# F1C100S.net
KiCad netlist of a schematic drawn in Altium Designer
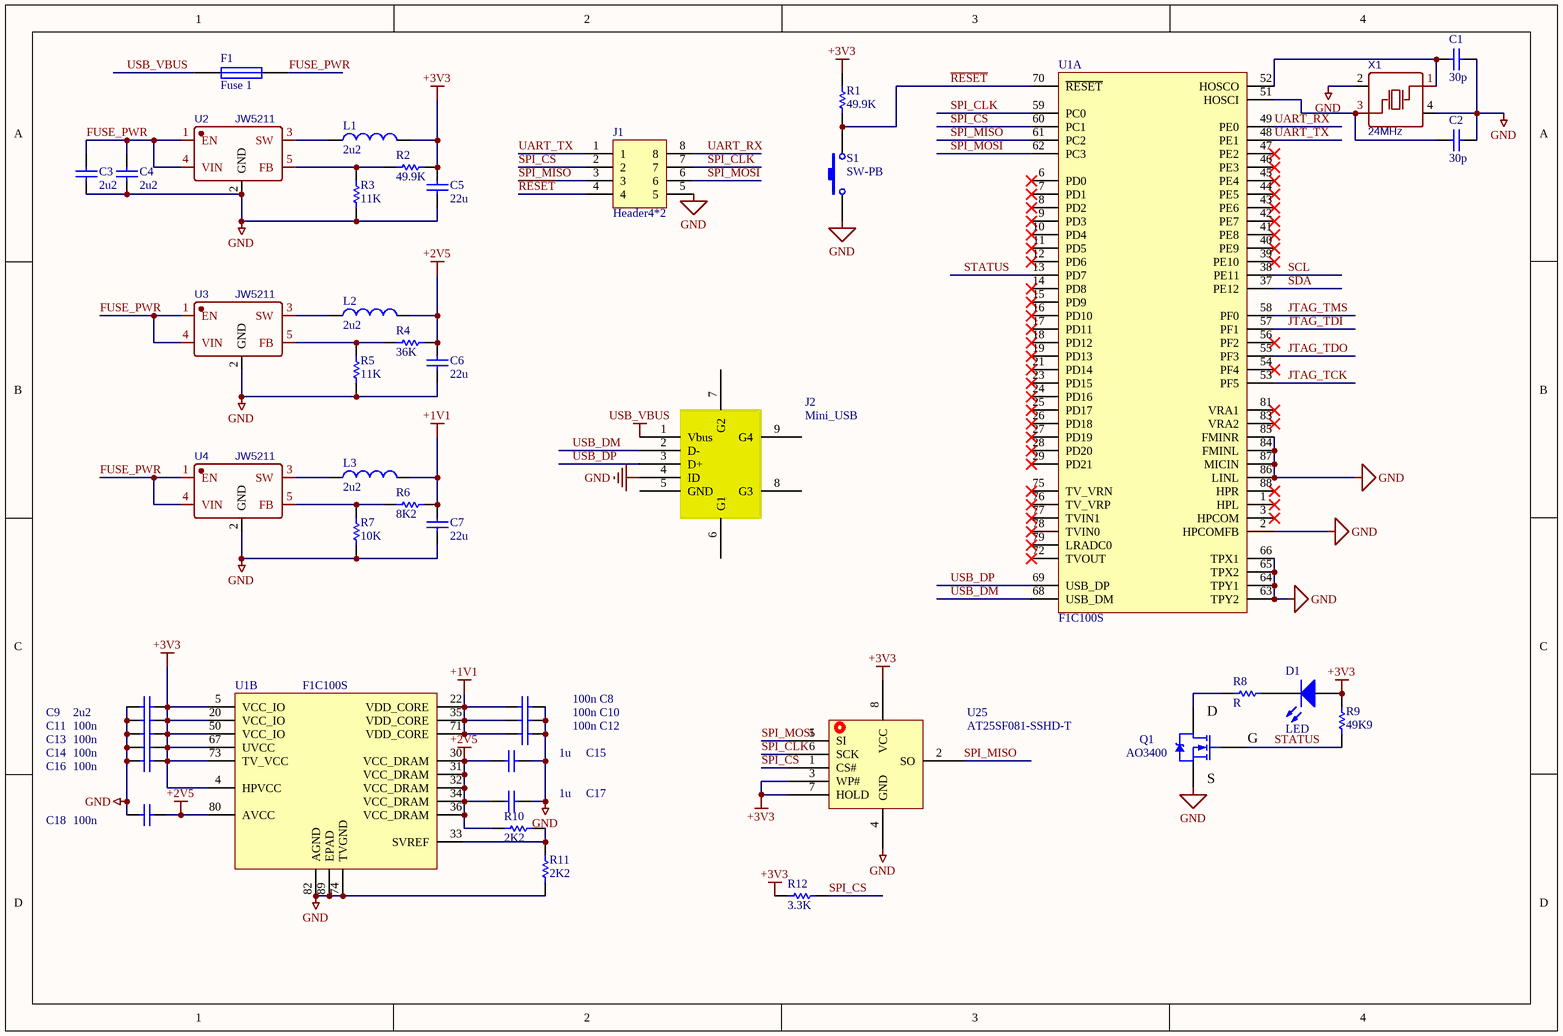
[diagram p0: 树莓派F1C100S.SchDoc]

(export (version "E")
  (design (tool "Eeschema 10.0.6"))
  (components
    (comp (ref "C1")
      (value "30p")
      (footprint "C0805")
      (description "Capacitor")
      (fields (field (name "PUBLISHER") "Altium Limited"))
      (libsource (lib "Miscellaneous Devices") (part "Cap"))
    )
    (comp (ref "C2")
      (value "30p")
      (footprint "C0805")
      (description "Capacitor")
      (fields (field (name "PUBLISHER") "Altium Limited"))
      (libsource (lib "Miscellaneous Devices") (part "Cap"))
    )
    (comp (ref "C3")
      (value "2u2")
      (footprint "C0805")
      (description "Capacitor")
      (fields (field (name "PUBLISHER") "Altium Limited"))
      (libsource (lib "Miscellaneous Devices") (part "Cap"))
    )
    (comp (ref "C4")
      (value "2u2")
      (footprint "C0805")
      (description "Capacitor")
      (fields (field (name "PUBLISHER") "Altium Limited"))
      (libsource (lib "Miscellaneous Devices") (part "Cap"))
    )
    (comp (ref "C5")
      (value "22u")
      (footprint "C0805")
      (description "Capacitor")
      (fields (field (name "PUBLISHER") "Altium Limited"))
      (libsource (lib "Miscellaneous Devices") (part "Cap"))
    )
    (comp (ref "C6")
      (value "22u")
      (footprint "C0805")
      (description "Capacitor")
      (fields (field (name "PUBLISHER") "Altium Limited"))
      (libsource (lib "Miscellaneous Devices") (part "Cap"))
    )
    (comp (ref "C7")
      (value "22u")
      (footprint "C0805")
      (description "Capacitor")
      (fields (field (name "PUBLISHER") "Altium Limited"))
      (libsource (lib "Miscellaneous Devices") (part "Cap"))
    )
    (comp (ref "C8")
      (value "100n")
      (footprint "C0805")
      (description "Capacitor")
      (fields (field (name "PUBLISHER") "Altium Limited"))
      (libsource (lib "Miscellaneous Devices") (part "Cap"))
    )
    (comp (ref "C9")
      (value "2u2")
      (footprint "C0805")
      (description "Capacitor")
      (fields (field (name "PUBLISHER") "Altium Limited"))
      (libsource (lib "Miscellaneous Devices") (part "Cap"))
    )
    (comp (ref "C10")
      (value "100n")
      (footprint "C0805")
      (description "Capacitor")
      (fields (field (name "PUBLISHER") "Altium Limited"))
      (libsource (lib "Miscellaneous Devices") (part "Cap"))
    )
    (comp (ref "C11")
      (value "100n")
      (footprint "C0805")
      (description "Capacitor")
      (fields (field (name "PUBLISHER") "Altium Limited"))
      (libsource (lib "Miscellaneous Devices") (part "Cap"))
    )
    (comp (ref "C12")
      (value "100n")
      (footprint "C0805")
      (description "Capacitor")
      (fields (field (name "PUBLISHER") "Altium Limited"))
      (libsource (lib "Miscellaneous Devices") (part "Cap"))
    )
    (comp (ref "C13")
      (value "100n")
      (footprint "C0805")
      (description "Capacitor")
      (fields (field (name "PUBLISHER") "Altium Limited"))
      (libsource (lib "Miscellaneous Devices") (part "Cap"))
    )
    (comp (ref "C14")
      (value "100n")
      (footprint "C0805")
      (description "Capacitor")
      (fields (field (name "PUBLISHER") "Altium Limited"))
      (libsource (lib "Miscellaneous Devices") (part "Cap"))
    )
    (comp (ref "C15")
      (value "1u")
      (footprint "C0805")
      (description "Capacitor")
      (fields (field (name "PUBLISHER") "Altium Limited"))
      (libsource (lib "Miscellaneous Devices") (part "Cap"))
    )
    (comp (ref "C16")
      (value "100n")
      (footprint "C0805")
      (description "Capacitor")
      (fields (field (name "PUBLISHER") "Altium Limited"))
      (libsource (lib "Miscellaneous Devices") (part "Cap"))
    )
    (comp (ref "C17")
      (value "1u")
      (footprint "C0805")
      (description "Capacitor")
      (fields (field (name "PUBLISHER") "Altium Limited"))
      (libsource (lib "Miscellaneous Devices") (part "Cap"))
    )
    (comp (ref "C18")
      (value "100n")
      (footprint "C0805")
      (description "Capacitor")
      (fields (field (name "PUBLISHER") "Altium Limited"))
      (libsource (lib "Miscellaneous Devices") (part "Cap"))
    )
    (comp (ref "D1")
      (value "LED")
      (footprint "LED-0805")
      (description "Typical INFRARED GaAs LED")
      (fields (field (name "PUBLISHER") "Altium Limited"))
      (libsource (lib "SZ") (part "LED0"))
    )
    (comp (ref "F1")
      (value "Fuse 1")
      (footprint "polyfuse")
      (description "Fuse")
      (fields (field (name "PUBLISHER") "Altium Limited"))
      (libsource (lib "Miscellaneous Devices") (part "Fuse 1"))
    )
    (comp (ref "J1") (value "Header4*2") (footprint "HDR2X4") (libsource (lib "SZ") (part "Header4*2")))
    (comp (ref "J2") (value "Mini_USB") (footprint "MINi_USB_2") (libsource (lib "*") (part "Mini_USB")))
    (comp (ref "L1")
      (value "2u2")
      (footprint "R0805")
      (description "Inductor")
      (fields (field (name "PUBLISHER") "Altium Limited"))
      (libsource (lib "Miscellaneous Devices") (part "Inductor"))
    )
    (comp (ref "L2")
      (value "2u2")
      (footprint "R0805")
      (description "Inductor")
      (fields (field (name "PUBLISHER") "Altium Limited"))
      (libsource (lib "Miscellaneous Devices") (part "Inductor"))
    )
    (comp (ref "L3")
      (value "2u2")
      (footprint "R0805")
      (description "Inductor")
      (fields (field (name "PUBLISHER") "Altium Limited"))
      (libsource (lib "Miscellaneous Devices") (part "Inductor"))
    )
    (comp (ref "Q1")
      (value "AO3400")
      (footprint "SOT-23")
      (description "N-Channel Power MOSFET")
      (fields (field (name "PUBLISHER") "Altium Limited"))
      (libsource (lib "SZ") (part "AO3400"))
    )
    (comp (ref "R1")
      (value "49.9K")
      (footprint "R0805")
      (description "Resistor")
      (fields (field (name "PUBLISHER") "Altium Limited"))
      (libsource (lib "Miscellaneous Devices") (part "Res1"))
    )
    (comp (ref "R2")
      (value "49.9K")
      (footprint "R0805")
      (description "Resistor")
      (fields (field (name "PUBLISHER") "Altium Limited"))
      (libsource (lib "Miscellaneous Devices") (part "Res1"))
    )
    (comp (ref "R3")
      (value "11K")
      (footprint "R0805")
      (description "Resistor")
      (fields (field (name "PUBLISHER") "Altium Limited"))
      (libsource (lib "Miscellaneous Devices") (part "Res1"))
    )
    (comp (ref "R4")
      (value "36K")
      (footprint "R0805")
      (description "Resistor")
      (fields (field (name "PUBLISHER") "Altium Limited"))
      (libsource (lib "Miscellaneous Devices") (part "Res1"))
    )
    (comp (ref "R5")
      (value "11K")
      (footprint "R0805")
      (description "Resistor")
      (fields (field (name "PUBLISHER") "Altium Limited"))
      (libsource (lib "Miscellaneous Devices") (part "Res1"))
    )
    (comp (ref "R6")
      (value "8K2")
      (footprint "R0805")
      (description "Resistor")
      (fields (field (name "PUBLISHER") "Altium Limited"))
      (libsource (lib "Miscellaneous Devices") (part "Res1"))
    )
    (comp (ref "R7")
      (value "10K")
      (footprint "R0805")
      (description "Resistor")
      (fields (field (name "PUBLISHER") "Altium Limited"))
      (libsource (lib "Miscellaneous Devices") (part "Res1"))
    )
    (comp (ref "R8")
      (value "R")
      (footprint "R0805")
      (description "Resistor")
      (fields (field (name "PUBLISHER") "Altium Limited"))
      (libsource (lib "Miscellaneous Devices") (part "Res1"))
    )
    (comp (ref "R9")
      (value "49K9")
      (footprint "R0805")
      (description "Resistor")
      (fields (field (name "PUBLISHER") "Altium Limited"))
      (libsource (lib "Miscellaneous Devices") (part "Res1"))
    )
    (comp (ref "R10")
      (value "2K2")
      (footprint "R0805")
      (description "Resistor")
      (fields (field (name "PUBLISHER") "Altium Limited"))
      (libsource (lib "Miscellaneous Devices") (part "Res1"))
    )
    (comp (ref "R11")
      (value "2K2")
      (footprint "R0805")
      (description "Resistor")
      (fields (field (name "PUBLISHER") "Altium Limited"))
      (libsource (lib "Miscellaneous Devices") (part "Res1"))
    )
    (comp (ref "R12")
      (value "3.3K")
      (footprint "R0805")
      (description "Resistor")
      (fields (field (name "PUBLISHER") "Altium Limited"))
      (libsource (lib "Miscellaneous Devices") (part "Res1"))
    )
    (comp (ref "S1")
      (value "SW-PB")
      (footprint "SW-2")
      (description "Switch")
      (fields (field (name "PUBLISHER") "Altium Limited"))
      (libsource (lib "Miscellaneous Devices") (part "SW-PB"))
    )
    (comp (ref "U1")
      (value "F1C100S")
      (footprint "QFN-88")
      (description "树莓派 全志")
      (libsource (lib "SZ") (part "F1C100S"))
    )
    (comp (ref "U2")
      (value "JW5211")
      (footprint "SOT-23-5")
      (fields (field (name "BOM_SUPPLIER PART") "C371423") (field (name "CONTRIBUTOR") "LCSC"))
      (libsource (lib "立创原理图库") (part "JW5211"))
    )
    (comp (ref "U3")
      (value "JW5211")
      (footprint "SOT-23-5")
      (fields (field (name "BOM_SUPPLIER PART") "C371423") (field (name "CONTRIBUTOR") "LCSC"))
      (libsource (lib "立创原理图库") (part "JW5211"))
    )
    (comp (ref "U4")
      (value "JW5211")
      (footprint "SOT-23-5")
      (fields (field (name "BOM_SUPPLIER PART") "C371423") (field (name "CONTRIBUTOR") "LCSC"))
      (libsource (lib "立创原理图库") (part "JW5211"))
    )
    (comp (ref "U25")
      (value "AT25SF081-SSHD-T")
      (footprint "AT25SF081-SSHD-T")
      (libsource (lib "Dr.Xiong_20160818") (part "AT25SF081-SSHD-T"))
    )
    (comp (ref "X1")
      (value "24MHz")
      (footprint "5032_4P_24M")
      (fields
        (field (name "BOM_SUPPLIER PART") "C156248")
        (field (name "BOM_MANUFACTURER PART") "NX3225GA-24MHZ(STD-CRG-2)")
        (field (name "CONTRIBUTOR") "LCSC")
      )
      (libsource (lib "立创原理图库") (part "24MHz"))
    )
  )
  (nets
    (net (code "1") (name "+1V1") (class "Default")
      (node (ref "C10") (pin "1") (pinfunction "1_1") (pintype "passive"))
      (node (ref "C12") (pin "1") (pinfunction "1_1") (pintype "passive"))
      (node (ref "C7") (pin "2") (pinfunction "2_2") (pintype "passive"))
      (node (ref "C8") (pin "1") (pinfunction "1_1") (pintype "passive"))
      (node (ref "L3") (pin "2") (pinfunction "2_2") (pintype "passive"))
      (node (ref "R6") (pin "1") (pinfunction "1_1") (pintype "passive"))
      (node (ref "U1") (pin "22") (pinfunction "VDD_CORE_22") (pintype "passive"))
      (node (ref "U1") (pin "35") (pinfunction "VDD_CORE_35") (pintype "passive"))
      (node (ref "U1") (pin "71") (pinfunction "VDD_CORE_71") (pintype "passive"))
    )
    (net (code "2") (name "+2V5") (class "Default")
      (node (ref "C15") (pin "1") (pinfunction "1_1") (pintype "passive"))
      (node (ref "C17") (pin "1") (pinfunction "1_1") (pintype "passive"))
      (node (ref "C18") (pin "1") (pinfunction "1_1") (pintype "passive"))
      (node (ref "C6") (pin "2") (pinfunction "2_2") (pintype "passive"))
      (node (ref "L2") (pin "2") (pinfunction "2_2") (pintype "passive"))
      (node (ref "R10") (pin "2") (pinfunction "2_2") (pintype "passive"))
      (node (ref "R4") (pin "1") (pinfunction "1_1") (pintype "passive"))
      (node (ref "U1") (pin "30") (pinfunction "VCC_DRAM_30") (pintype "passive"))
      (node (ref "U1") (pin "31") (pinfunction "VCC_DRAM_31") (pintype "passive"))
      (node (ref "U1") (pin "32") (pinfunction "VCC_DRAM_32") (pintype "passive"))
      (node (ref "U1") (pin "34") (pinfunction "VCC_DRAM_34") (pintype "passive"))
      (node (ref "U1") (pin "36") (pinfunction "VCC_DRAM_36") (pintype "passive"))
      (node (ref "U1") (pin "80") (pinfunction "AVCC_80") (pintype "passive"))
    )
    (net (code "3") (name "+3V3") (class "Default")
      (node (ref "C11") (pin "1") (pinfunction "1_1") (pintype "passive"))
      (node (ref "C13") (pin "1") (pinfunction "1_1") (pintype "passive"))
      (node (ref "C14") (pin "1") (pinfunction "1_1") (pintype "passive"))
      (node (ref "C16") (pin "1") (pinfunction "1_1") (pintype "passive"))
      (node (ref "C5") (pin "2") (pinfunction "2_2") (pintype "passive"))
      (node (ref "C9") (pin "1") (pinfunction "1_1") (pintype "passive"))
      (node (ref "D1") (pin "1") (pinfunction "A_1") (pintype "passive"))
      (node (ref "L1") (pin "2") (pinfunction "2_2") (pintype "passive"))
      (node (ref "R1") (pin "1") (pinfunction "1_1") (pintype "passive"))
      (node (ref "R12") (pin "1") (pinfunction "1_1") (pintype "passive"))
      (node (ref "R2") (pin "1") (pinfunction "1_1") (pintype "passive"))
      (node (ref "R9") (pin "2") (pinfunction "2_2") (pintype "passive"))
      (node (ref "U1") (pin "20") (pinfunction "VCC_IO_20") (pintype "passive"))
      (node (ref "U1") (pin "4") (pinfunction "HPVCC_4") (pintype "passive"))
      (node (ref "U1") (pin "5") (pinfunction "VCC_IO_5") (pintype "passive"))
      (node (ref "U1") (pin "50") (pinfunction "VCC_IO_50") (pintype "passive"))
      (node (ref "U1") (pin "67") (pinfunction "UVCC_67") (pintype "passive"))
      (node (ref "U1") (pin "73") (pinfunction "TV_VCC_73") (pintype "passive"))
      (node (ref "U25") (pin "3") (pinfunction "WP#_3") (pintype "passive"))
      (node (ref "U25") (pin "7") (pinfunction "HOLD_7") (pintype "passive"))
      (node (ref "U25") (pin "8") (pinfunction "VCC_8") (pintype "passive"))
    )
    (net (code "4") (name "/FUSE_PWR") (class "Default")
      (node (ref "C3") (pin "2") (pinfunction "2_2") (pintype "passive"))
      (node (ref "C4") (pin "2") (pinfunction "2_2") (pintype "passive"))
      (node (ref "F1") (pin "2") (pinfunction "2_2") (pintype "passive"))
      (node (ref "U2") (pin "1") (pinfunction "EN_1") (pintype "passive"))
      (node (ref "U2") (pin "4") (pinfunction "VIN_4") (pintype "passive"))
      (node (ref "U3") (pin "1") (pinfunction "EN_1") (pintype "passive"))
      (node (ref "U3") (pin "4") (pinfunction "VIN_4") (pintype "passive"))
      (node (ref "U4") (pin "1") (pinfunction "EN_1") (pintype "passive"))
      (node (ref "U4") (pin "4") (pinfunction "VIN_4") (pintype "passive"))
    )
    (net (code "5") (name "/JTAG_TCK") (class "Default")
      (node (ref "U1") (pin "53") (pinfunction "PF5_53") (pintype "passive"))
    )
    (net (code "6") (name "/JTAG_TDI") (class "Default")
      (node (ref "U1") (pin "57") (pinfunction "PF1_57") (pintype "passive"))
    )
    (net (code "7") (name "/JTAG_TDO") (class "Default")
      (node (ref "U1") (pin "55") (pinfunction "PF3_55") (pintype "passive"))
    )
    (net (code "8") (name "/JTAG_TMS") (class "Default")
      (node (ref "U1") (pin "58") (pinfunction "PF0_58") (pintype "passive"))
    )
    (net (code "9") (name "/SCL") (class "Default")
      (node (ref "U1") (pin "38") (pinfunction "PE11_38") (pintype "passive"))
    )
    (net (code "10") (name "/SDA") (class "Default")
      (node (ref "U1") (pin "37") (pinfunction "PE12_37") (pintype "passive"))
    )
    (net (code "11") (name "/SPI_CLK") (class "Default")
      (node (ref "J1") (pin "7") (pinfunction "7_7") (pintype "passive"))
      (node (ref "U1") (pin "59") (pinfunction "PC0_59") (pintype "passive"))
      (node (ref "U25") (pin "6") (pinfunction "SCK_6") (pintype "passive"))
    )
    (net (code "12") (name "/SPI_CS") (class "Default")
      (node (ref "J1") (pin "2") (pinfunction "2_2") (pintype "passive"))
      (node (ref "R12") (pin "2") (pinfunction "2_2") (pintype "passive"))
      (node (ref "U1") (pin "60") (pinfunction "PC1_60") (pintype "passive"))
      (node (ref "U25") (pin "1") (pinfunction "CS#_1") (pintype "passive"))
    )
    (net (code "13") (name "/SPI_MISO") (class "Default")
      (node (ref "J1") (pin "3") (pinfunction "3_3") (pintype "passive"))
      (node (ref "U1") (pin "61") (pinfunction "PC2_61") (pintype "passive"))
      (node (ref "U25") (pin "2") (pinfunction "SO_2") (pintype "passive"))
    )
    (net (code "14") (name "/SPI_MOSI") (class "Default")
      (node (ref "J1") (pin "6") (pinfunction "6_6") (pintype "passive"))
      (node (ref "U1") (pin "62") (pinfunction "PC3_62") (pintype "passive"))
      (node (ref "U25") (pin "5") (pinfunction "SI_5") (pintype "passive"))
    )
    (net (code "15") (name "/STATUS") (class "Default")
      (node (ref "Q1") (pin "1") (pinfunction "G_1") (pintype "passive"))
      (node (ref "R9") (pin "1") (pinfunction "1_1") (pintype "passive"))
      (node (ref "U1") (pin "13") (pinfunction "PD7_13") (pintype "passive"))
    )
    (net (code "16") (name "/UART_RX") (class "Default")
      (node (ref "J1") (pin "8") (pinfunction "8_8") (pintype "passive"))
      (node (ref "U1") (pin "49") (pinfunction "PE0_49") (pintype "passive"))
    )
    (net (code "17") (name "/UART_TX") (class "Default")
      (node (ref "J1") (pin "1") (pinfunction "1_1") (pintype "passive"))
      (node (ref "U1") (pin "48") (pinfunction "PE1_48") (pintype "passive"))
    )
    (net (code "18") (name "/USB_DM") (class "Default")
      (node (ref "J2") (pin "2") (pinfunction "D-_2") (pintype "passive"))
      (node (ref "U1") (pin "68") (pinfunction "USB_DM_68") (pintype "passive"))
    )
    (net (code "19") (name "/USB_DP") (class "Default")
      (node (ref "J2") (pin "3") (pinfunction "D+_3") (pintype "passive"))
      (node (ref "U1") (pin "69") (pinfunction "USB_DP_69") (pintype "passive"))
    )
    (net (code "20") (name "/~{RESET}") (class "Default")
      (node (ref "J1") (pin "4") (pinfunction "4_4") (pintype "passive"))
      (node (ref "R1") (pin "2") (pinfunction "2_2") (pintype "passive"))
      (node (ref "S1") (pin "2") (pinfunction "2_2") (pintype "passive"))
      (node (ref "U1") (pin "70") (pinfunction "~{RESET}_70") (pintype "passive"))
    )
    (net (code "21") (name "GND") (class "Default")
      (node (ref "C1") (pin "2") (pinfunction "2_2") (pintype "passive"))
      (node (ref "C10") (pin "2") (pinfunction "2_2") (pintype "passive"))
      (node (ref "C11") (pin "2") (pinfunction "2_2") (pintype "passive"))
      (node (ref "C12") (pin "2") (pinfunction "2_2") (pintype "passive"))
      (node (ref "C13") (pin "2") (pinfunction "2_2") (pintype "passive"))
      (node (ref "C14") (pin "2") (pinfunction "2_2") (pintype "passive"))
      (node (ref "C15") (pin "2") (pinfunction "2_2") (pintype "passive"))
      (node (ref "C16") (pin "2") (pinfunction "2_2") (pintype "passive"))
      (node (ref "C17") (pin "2") (pinfunction "2_2") (pintype "passive"))
      (node (ref "C18") (pin "2") (pinfunction "2_2") (pintype "passive"))
      (node (ref "C2") (pin "2") (pinfunction "2_2") (pintype "passive"))
      (node (ref "C3") (pin "1") (pinfunction "1_1") (pintype "passive"))
      (node (ref "C4") (pin "1") (pinfunction "1_1") (pintype "passive"))
      (node (ref "C5") (pin "1") (pinfunction "1_1") (pintype "passive"))
      (node (ref "C6") (pin "1") (pinfunction "1_1") (pintype "passive"))
      (node (ref "C7") (pin "1") (pinfunction "1_1") (pintype "passive"))
      (node (ref "C8") (pin "2") (pinfunction "2_2") (pintype "passive"))
      (node (ref "C9") (pin "2") (pinfunction "2_2") (pintype "passive"))
      (node (ref "J1") (pin "5") (pinfunction "5_5") (pintype "passive"))
      (node (ref "J2") (pin "4") (pinfunction "ID_4") (pintype "passive"))
      (node (ref "Q1") (pin "2") (pinfunction "S_2") (pintype "passive"))
      (node (ref "R11") (pin "2") (pinfunction "2_2") (pintype "passive"))
      (node (ref "R3") (pin "1") (pinfunction "1_1") (pintype "passive"))
      (node (ref "R5") (pin "1") (pinfunction "1_1") (pintype "passive"))
      (node (ref "R7") (pin "1") (pinfunction "1_1") (pintype "passive"))
      (node (ref "S1") (pin "1") (pinfunction "1_1") (pintype "passive"))
      (node (ref "U1") (pin "2") (pinfunction "HPCOMFB_2") (pintype "passive"))
      (node (ref "U1") (pin "63") (pinfunction "TPY2_63") (pintype "passive"))
      (node (ref "U1") (pin "64") (pinfunction "TPY1_64") (pintype "passive"))
      (node (ref "U1") (pin "65") (pinfunction "TPX2_65") (pintype "passive"))
      (node (ref "U1") (pin "66") (pinfunction "TPX1_66") (pintype "passive"))
      (node (ref "U1") (pin "74") (pinfunction "TVGND_74") (pintype "passive"))
      (node (ref "U1") (pin "82") (pinfunction "AGND_82") (pintype "passive"))
      (node (ref "U1") (pin "84") (pinfunction "FMINL_84") (pintype "passive"))
      (node (ref "U1") (pin "85") (pinfunction "FMINR_85") (pintype "passive"))
      (node (ref "U1") (pin "86") (pinfunction "LINL_86") (pintype "passive"))
      (node (ref "U1") (pin "87") (pinfunction "MICIN_87") (pintype "passive"))
      (node (ref "U1") (pin "89") (pinfunction "EPAD_89") (pintype "passive"))
      (node (ref "U2") (pin "2") (pinfunction "GND_2") (pintype "passive"))
      (node (ref "U25") (pin "4") (pinfunction "GND_4") (pintype "passive"))
      (node (ref "U3") (pin "2") (pinfunction "GND_2") (pintype "passive"))
      (node (ref "U4") (pin "2") (pinfunction "GND_2") (pintype "passive"))
      (node (ref "X1") (pin "2") (pinfunction "2_2") (pintype "passive"))
      (node (ref "X1") (pin "4") (pinfunction "4_4") (pintype "passive"))
    )
    (net (code "22") (name "Net-(D1-K)") (class "Default")
      (node (ref "D1") (pin "2") (pinfunction "K_2") (pintype "passive"))
      (node (ref "R8") (pin "2") (pinfunction "2_2") (pintype "passive"))
    )
    (net (code "23") (name "Net-(Q1-D)") (class "Default")
      (node (ref "Q1") (pin "3") (pinfunction "D_3") (pintype "passive"))
      (node (ref "R8") (pin "1") (pinfunction "1_1") (pintype "passive"))
    )
    (net (code "24") (name "Net-(U1A-HOSCI)") (class "Default")
      (node (ref "C2") (pin "1") (pinfunction "1_1") (pintype "passive"))
      (node (ref "U1") (pin "51") (pinfunction "HOSCI_51") (pintype "passive"))
      (node (ref "X1") (pin "3") (pinfunction "OSC2_3") (pintype "passive"))
    )
    (net (code "25") (name "Net-(U1A-HOSCO)") (class "Default")
      (node (ref "C1") (pin "1") (pinfunction "1_1") (pintype "passive"))
      (node (ref "U1") (pin "52") (pinfunction "HOSCO_52") (pintype "passive"))
      (node (ref "X1") (pin "1") (pinfunction "OSC1_1") (pintype "passive"))
    )
    (net (code "26") (name "Net-(U1B-SVREF)") (class "Default")
      (node (ref "R10") (pin "1") (pinfunction "1_1") (pintype "passive"))
      (node (ref "R11") (pin "1") (pinfunction "1_1") (pintype "passive"))
      (node (ref "U1") (pin "33") (pinfunction "SVREF_33") (pintype "passive"))
    )
    (net (code "27") (name "Net-(U2-FB)") (class "Default")
      (node (ref "R2") (pin "2") (pinfunction "2_2") (pintype "passive"))
      (node (ref "R3") (pin "2") (pinfunction "2_2") (pintype "passive"))
      (node (ref "U2") (pin "5") (pinfunction "FB_5") (pintype "passive"))
    )
    (net (code "28") (name "Net-(U2-SW)") (class "Default")
      (node (ref "L1") (pin "1") (pinfunction "1_1") (pintype "passive"))
      (node (ref "U2") (pin "3") (pinfunction "SW_3") (pintype "passive"))
    )
    (net (code "29") (name "Net-(U3-FB)") (class "Default")
      (node (ref "R4") (pin "2") (pinfunction "2_2") (pintype "passive"))
      (node (ref "R5") (pin "2") (pinfunction "2_2") (pintype "passive"))
      (node (ref "U3") (pin "5") (pinfunction "FB_5") (pintype "passive"))
    )
    (net (code "30") (name "Net-(U3-SW)") (class "Default")
      (node (ref "L2") (pin "1") (pinfunction "1_1") (pintype "passive"))
      (node (ref "U3") (pin "3") (pinfunction "SW_3") (pintype "passive"))
    )
    (net (code "31") (name "Net-(U4-FB)") (class "Default")
      (node (ref "R6") (pin "2") (pinfunction "2_2") (pintype "passive"))
      (node (ref "R7") (pin "2") (pinfunction "2_2") (pintype "passive"))
      (node (ref "U4") (pin "5") (pinfunction "FB_5") (pintype "passive"))
    )
    (net (code "32") (name "Net-(U4-SW)") (class "Default")
      (node (ref "L3") (pin "1") (pinfunction "1_1") (pintype "passive"))
      (node (ref "U4") (pin "3") (pinfunction "SW_3") (pintype "passive"))
    )
    (net (code "33") (name "USB_VBUS") (class "Default")
      (node (ref "F1") (pin "1") (pinfunction "1_1") (pintype "passive"))
      (node (ref "J2") (pin "1") (pinfunction "Vbus_1") (pintype "passive"))
    )
    (net (code "34") (name "unconnected-(J2-G1-Pad6)") (class "Default")
      (node (ref "J2") (pin "6") (pinfunction "G1_6") (pintype "passive"))
    )
    (net (code "35") (name "unconnected-(J2-G2-Pad7)") (class "Default")
      (node (ref "J2") (pin "7") (pinfunction "G2_7") (pintype "passive"))
    )
    (net (code "36") (name "unconnected-(J2-G3-Pad8)") (class "Default")
      (node (ref "J2") (pin "8") (pinfunction "G3_8") (pintype "passive"))
    )
    (net (code "37") (name "unconnected-(J2-G4-Pad9)") (class "Default")
      (node (ref "J2") (pin "9") (pinfunction "G4_9") (pintype "passive"))
    )
    (net (code "38") (name "unconnected-(J2-GND-Pad5)") (class "Default")
      (node (ref "J2") (pin "5") (pinfunction "GND_5") (pintype "passive"))
    )
    (net (code "39") (name "unconnected-(U1A-HPCOM-Pad3)") (class "Default")
      (node (ref "U1") (pin "3") (pinfunction "HPCOM_3") (pintype "passive+no_connect"))
    )
    (net (code "40") (name "unconnected-(U1A-HPL-Pad1)") (class "Default")
      (node (ref "U1") (pin "1") (pinfunction "HPL_1") (pintype "passive+no_connect"))
    )
    (net (code "41") (name "unconnected-(U1A-HPR-Pad88)") (class "Default")
      (node (ref "U1") (pin "88") (pinfunction "HPR_88") (pintype "passive+no_connect"))
    )
    (net (code "42") (name "unconnected-(U1A-LRADC0-Pad79)") (class "Default")
      (node (ref "U1") (pin "79") (pinfunction "LRADC0_79") (pintype "passive+no_connect"))
    )
    (net (code "43") (name "unconnected-(U1A-PD0-Pad6)") (class "Default")
      (node (ref "U1") (pin "6") (pinfunction "PD0_6") (pintype "passive+no_connect"))
    )
    (net (code "44") (name "unconnected-(U1A-PD1-Pad7)") (class "Default")
      (node (ref "U1") (pin "7") (pinfunction "PD1_7") (pintype "passive+no_connect"))
    )
    (net (code "45") (name "unconnected-(U1A-PD2-Pad8)") (class "Default")
      (node (ref "U1") (pin "8") (pinfunction "PD2_8") (pintype "passive+no_connect"))
    )
    (net (code "46") (name "unconnected-(U1A-PD3-Pad9)") (class "Default")
      (node (ref "U1") (pin "9") (pinfunction "PD3_9") (pintype "passive+no_connect"))
    )
    (net (code "47") (name "unconnected-(U1A-PD4-Pad10)") (class "Default")
      (node (ref "U1") (pin "10") (pinfunction "PD4_10") (pintype "passive+no_connect"))
    )
    (net (code "48") (name "unconnected-(U1A-PD5-Pad11)") (class "Default")
      (node (ref "U1") (pin "11") (pinfunction "PD5_11") (pintype "passive+no_connect"))
    )
    (net (code "49") (name "unconnected-(U1A-PD6-Pad12)") (class "Default")
      (node (ref "U1") (pin "12") (pinfunction "PD6_12") (pintype "passive+no_connect"))
    )
    (net (code "50") (name "unconnected-(U1A-PD8-Pad14)") (class "Default")
      (node (ref "U1") (pin "14") (pinfunction "PD8_14") (pintype "passive+no_connect"))
    )
    (net (code "51") (name "unconnected-(U1A-PD9-Pad15)") (class "Default")
      (node (ref "U1") (pin "15") (pinfunction "PD9_15") (pintype "passive+no_connect"))
    )
    (net (code "52") (name "unconnected-(U1A-PD10-Pad16)") (class "Default")
      (node (ref "U1") (pin "16") (pinfunction "PD10_16") (pintype "passive+no_connect"))
    )
    (net (code "53") (name "unconnected-(U1A-PD11-Pad17)") (class "Default")
      (node (ref "U1") (pin "17") (pinfunction "PD11_17") (pintype "passive+no_connect"))
    )
    (net (code "54") (name "unconnected-(U1A-PD12-Pad18)") (class "Default")
      (node (ref "U1") (pin "18") (pinfunction "PD12_18") (pintype "passive+no_connect"))
    )
    (net (code "55") (name "unconnected-(U1A-PD13-Pad19)") (class "Default")
      (node (ref "U1") (pin "19") (pinfunction "PD13_19") (pintype "passive+no_connect"))
    )
    (net (code "56") (name "unconnected-(U1A-PD14-Pad21)") (class "Default")
      (node (ref "U1") (pin "21") (pinfunction "PD14_21") (pintype "passive+no_connect"))
    )
    (net (code "57") (name "unconnected-(U1A-PD15-Pad23)") (class "Default")
      (node (ref "U1") (pin "23") (pinfunction "PD15_23") (pintype "passive+no_connect"))
    )
    (net (code "58") (name "unconnected-(U1A-PD16-Pad24)") (class "Default")
      (node (ref "U1") (pin "24") (pinfunction "PD16_24") (pintype "passive+no_connect"))
    )
    (net (code "59") (name "unconnected-(U1A-PD17-Pad25)") (class "Default")
      (node (ref "U1") (pin "25") (pinfunction "PD17_25") (pintype "passive+no_connect"))
    )
    (net (code "60") (name "unconnected-(U1A-PD18-Pad26)") (class "Default")
      (node (ref "U1") (pin "26") (pinfunction "PD18_26") (pintype "passive+no_connect"))
    )
    (net (code "61") (name "unconnected-(U1A-PD19-Pad27)") (class "Default")
      (node (ref "U1") (pin "27") (pinfunction "PD19_27") (pintype "passive+no_connect"))
    )
    (net (code "62") (name "unconnected-(U1A-PD20-Pad28)") (class "Default")
      (node (ref "U1") (pin "28") (pinfunction "PD20_28") (pintype "passive+no_connect"))
    )
    (net (code "63") (name "unconnected-(U1A-PD21-Pad29)") (class "Default")
      (node (ref "U1") (pin "29") (pinfunction "PD21_29") (pintype "passive+no_connect"))
    )
    (net (code "64") (name "unconnected-(U1A-PE2-Pad47)") (class "Default")
      (node (ref "U1") (pin "47") (pinfunction "PE2_47") (pintype "passive+no_connect"))
    )
    (net (code "65") (name "unconnected-(U1A-PE3-Pad46)") (class "Default")
      (node (ref "U1") (pin "46") (pinfunction "PE3_46") (pintype "passive+no_connect"))
    )
    (net (code "66") (name "unconnected-(U1A-PE4-Pad45)") (class "Default")
      (node (ref "U1") (pin "45") (pinfunction "PE4_45") (pintype "passive+no_connect"))
    )
    (net (code "67") (name "unconnected-(U1A-PE5-Pad44)") (class "Default")
      (node (ref "U1") (pin "44") (pinfunction "PE5_44") (pintype "passive+no_connect"))
    )
    (net (code "68") (name "unconnected-(U1A-PE6-Pad43)") (class "Default")
      (node (ref "U1") (pin "43") (pinfunction "PE6_43") (pintype "passive+no_connect"))
    )
    (net (code "69") (name "unconnected-(U1A-PE7-Pad42)") (class "Default")
      (node (ref "U1") (pin "42") (pinfunction "PE7_42") (pintype "passive+no_connect"))
    )
    (net (code "70") (name "unconnected-(U1A-PE8-Pad41)") (class "Default")
      (node (ref "U1") (pin "41") (pinfunction "PE8_41") (pintype "passive+no_connect"))
    )
    (net (code "71") (name "unconnected-(U1A-PE9-Pad40)") (class "Default")
      (node (ref "U1") (pin "40") (pinfunction "PE9_40") (pintype "passive+no_connect"))
    )
    (net (code "72") (name "unconnected-(U1A-PE10-Pad39)") (class "Default")
      (node (ref "U1") (pin "39") (pinfunction "PE10_39") (pintype "passive+no_connect"))
    )
    (net (code "73") (name "unconnected-(U1A-PF2-Pad56)") (class "Default")
      (node (ref "U1") (pin "56") (pinfunction "PF2_56") (pintype "passive+no_connect"))
    )
    (net (code "74") (name "unconnected-(U1A-PF4-Pad54)") (class "Default")
      (node (ref "U1") (pin "54") (pinfunction "PF4_54") (pintype "passive+no_connect"))
    )
    (net (code "75") (name "unconnected-(U1A-TVIN0-Pad78)") (class "Default")
      (node (ref "U1") (pin "78") (pinfunction "TVIN0_78") (pintype "passive+no_connect"))
    )
    (net (code "76") (name "unconnected-(U1A-TVIN1-Pad77)") (class "Default")
      (node (ref "U1") (pin "77") (pinfunction "TVIN1_77") (pintype "passive+no_connect"))
    )
    (net (code "77") (name "unconnected-(U1A-TVOUT-Pad72)") (class "Default")
      (node (ref "U1") (pin "72") (pinfunction "TVOUT_72") (pintype "passive+no_connect"))
    )
    (net (code "78") (name "unconnected-(U1A-TV_VRN-Pad75)") (class "Default")
      (node (ref "U1") (pin "75") (pinfunction "TV_VRN_75") (pintype "passive+no_connect"))
    )
    (net (code "79") (name "unconnected-(U1A-TV_VRP-Pad76)") (class "Default")
      (node (ref "U1") (pin "76") (pinfunction "TV_VRP_76") (pintype "passive+no_connect"))
    )
    (net (code "80") (name "unconnected-(U1A-VRA1-Pad81)") (class "Default")
      (node (ref "U1") (pin "81") (pinfunction "VRA1_81") (pintype "passive+no_connect"))
    )
    (net (code "81") (name "unconnected-(U1A-VRA2-Pad83)") (class "Default")
      (node (ref "U1") (pin "83") (pinfunction "VRA2_83") (pintype "passive+no_connect"))
    )
  )
)
